# OSCILLAR_HFB_V1p0_AFILT.net
KiCad netlist of a schematic drawn in Altium Designer
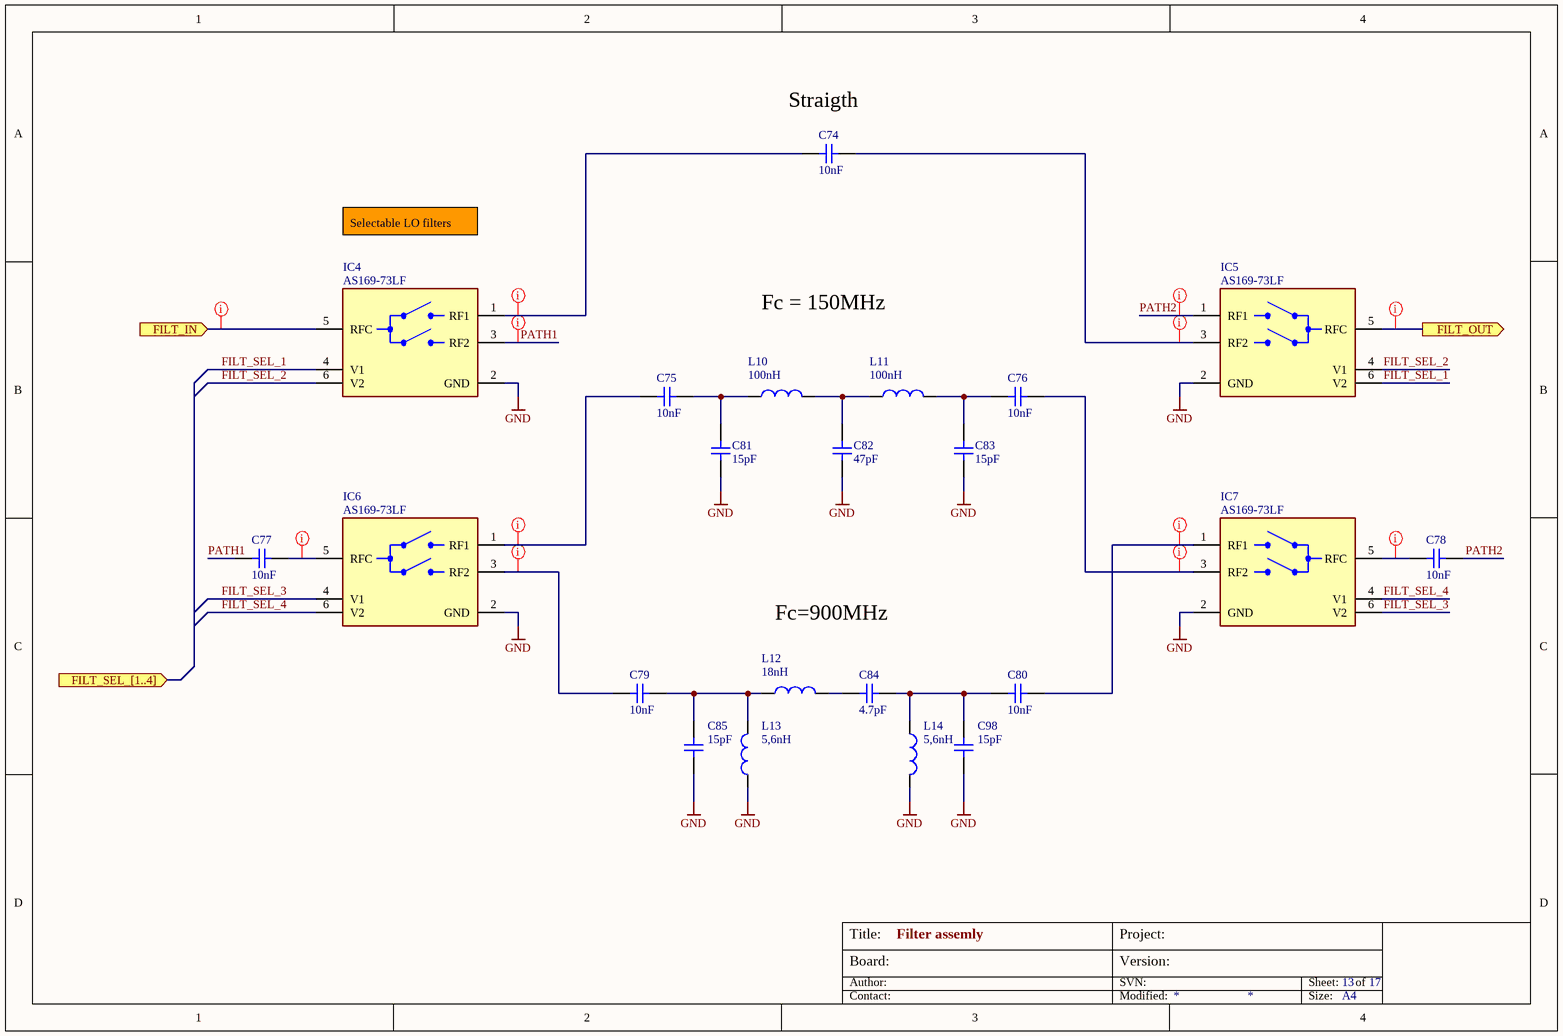
[diagram p0: OSCILLAR_HFB_V1p0_AFILT.SchDoc]

(export (version "E")
  (design (tool "Eeschema 10.0.6"))
  (components
    (comp (ref "C74")
      (value "10nF")
      (footprint "CAP_0603")
      (description "MLCC capacitor")
      (libsource (lib "SCHLIB") (part "NP-CAPACITOR"))
    )
    (comp (ref "C75")
      (value "10nF")
      (footprint "CAP_0603")
      (description "MLCC capacitor")
      (libsource (lib "SCHLIB") (part "NP-CAPACITOR"))
    )
    (comp (ref "C76")
      (value "10nF")
      (footprint "CAP_0603")
      (description "MLCC capacitor")
      (libsource (lib "SCHLIB") (part "NP-CAPACITOR"))
    )
    (comp (ref "C77")
      (value "10nF")
      (footprint "CAP_0603")
      (description "MLCC capacitor")
      (libsource (lib "SCHLIB") (part "NP-CAPACITOR"))
    )
    (comp (ref "C78")
      (value "10nF")
      (footprint "CAP_0603")
      (description "MLCC capacitor")
      (libsource (lib "SCHLIB") (part "NP-CAPACITOR"))
    )
    (comp (ref "C79")
      (value "10nF")
      (footprint "CAP_0603")
      (description "MLCC capacitor")
      (libsource (lib "SCHLIB") (part "NP-CAPACITOR"))
    )
    (comp (ref "C80")
      (value "10nF")
      (footprint "CAP_0603")
      (description "MLCC capacitor")
      (libsource (lib "SCHLIB") (part "NP-CAPACITOR"))
    )
    (comp (ref "C81")
      (value "15pF")
      (footprint "CAP_0603")
      (description "MLCC capacitor")
      (libsource (lib "SCHLIB") (part "NP-CAPACITOR"))
    )
    (comp (ref "C82")
      (value "47pF")
      (footprint "CAP_0603")
      (description "MLCC capacitor")
      (libsource (lib "SCHLIB") (part "NP-CAPACITOR"))
    )
    (comp (ref "C83")
      (value "15pF")
      (footprint "CAP_0603")
      (description "MLCC capacitor")
      (libsource (lib "SCHLIB") (part "NP-CAPACITOR"))
    )
    (comp (ref "C84")
      (value "4.7pF")
      (footprint "CAP_0603")
      (description "MLCC capacitor")
      (libsource (lib "SCHLIB") (part "NP-CAPACITOR"))
    )
    (comp (ref "C85")
      (value "15pF")
      (footprint "CAP_0603")
      (description "MLCC capacitor")
      (libsource (lib "SCHLIB") (part "NP-CAPACITOR"))
    )
    (comp (ref "C98")
      (value "15pF")
      (footprint "CAP_0603")
      (description "MLCC capacitor")
      (libsource (lib "SCHLIB") (part "NP-CAPACITOR"))
    )
    (comp (ref "IC4")
      (value "AS169-73LF")
      (footprint "SOT-23-6")
      (description "RF Switch, SPDT, 300k-2.5GHz")
      (fields (field (name "PART NUMBER") "873-AS169-73LF"))
      (libsource (lib "") (part "AS169-73LF_1"))
    )
    (comp (ref "IC5")
      (value "AS169-73LF")
      (footprint "SOT-23-6")
      (description "RF Switch, SPDT, 300k-2.5GHz")
      (fields (field (name "PART NUMBER") "873-AS169-73LF"))
      (libsource (lib "SCHLIB") (part "AS169-73LF"))
    )
    (comp (ref "IC6")
      (value "AS169-73LF")
      (footprint "SOT-23-6")
      (description "RF Switch, SPDT, 300k-2.5GHz")
      (fields (field (name "PART NUMBER") "873-AS169-73LF"))
      (libsource (lib "") (part "AS169-73LF_1"))
    )
    (comp (ref "IC7")
      (value "AS169-73LF")
      (footprint "SOT-23-6")
      (description "RF Switch, SPDT, 300k-2.5GHz")
      (fields (field (name "PART NUMBER") "873-AS169-73LF"))
      (libsource (lib "SCHLIB") (part "AS169-73LF"))
    )
    (comp (ref "L10")
      (value "100nH")
      (footprint "IND-0805")
      (description "IMC0805ERR10J01")
      (libsource (lib "SCHLIB") (part "AC-INDUCTOR"))
    )
    (comp (ref "L11")
      (value "100nH")
      (footprint "IND-0805")
      (description "IMC0805ERR10J01")
      (libsource (lib "SCHLIB") (part "AC-INDUCTOR"))
    )
    (comp (ref "L12")
      (value "18nH")
      (footprint "IND-0805")
      (description "IMC0805ER18NJ01")
      (libsource (lib "SCHLIB") (part "AC-INDUCTOR"))
    )
    (comp (ref "L13")
      (value "5,6nH")
      (footprint "IND-0805")
      (description "IMC0805ER5N6J01")
      (libsource (lib "SCHLIB") (part "AC-INDUCTOR"))
    )
    (comp (ref "L14")
      (value "5,6nH")
      (footprint "IND-0805")
      (description "IMC0805ER5N6J01")
      (libsource (lib "") (part "AC-INDUCTOR_1"))
    )
  )
  (nets
    (net (code "1") (name "/FILT_IN") (class "Default")
      (node (ref "IC4") (pin "5") (pinfunction "RFC_5") (pintype "passive"))
    )
    (net (code "2") (name "/FILT_OUT") (class "Default")
      (node (ref "IC5") (pin "5") (pinfunction "RFC_5") (pintype "passive"))
    )
    (net (code "3") (name "/FILT_SEL_1") (class "Default")
      (node (ref "IC4") (pin "4") (pinfunction "V1_4") (pintype "passive"))
      (node (ref "IC5") (pin "6") (pinfunction "V2_6") (pintype "passive"))
    )
    (net (code "4") (name "/FILT_SEL_2") (class "Default")
      (node (ref "IC4") (pin "6") (pinfunction "V2_6") (pintype "passive"))
      (node (ref "IC5") (pin "4") (pinfunction "V1_4") (pintype "passive"))
    )
    (net (code "5") (name "/FILT_SEL_3") (class "Default")
      (node (ref "IC6") (pin "4") (pinfunction "V1_4") (pintype "passive"))
      (node (ref "IC7") (pin "6") (pinfunction "V2_6") (pintype "passive"))
    )
    (net (code "6") (name "/FILT_SEL_4") (class "Default")
      (node (ref "IC6") (pin "6") (pinfunction "V2_6") (pintype "passive"))
      (node (ref "IC7") (pin "4") (pinfunction "V1_4") (pintype "passive"))
    )
    (net (code "8") (name "/PATH1") (class "Default")
      (node (ref "C77") (pin "2") (pinfunction "2_2") (pintype "passive"))
      (node (ref "IC4") (pin "3") (pinfunction "RF2_3") (pintype "passive"))
    )
    (net (code "9") (name "/PATH2") (class "Default")
      (node (ref "C78") (pin "1") (pinfunction "1_1") (pintype "passive"))
      (node (ref "IC5") (pin "1") (pinfunction "RF1_1") (pintype "passive"))
    )
    (net (code "10") (name "GND") (class "Default")
      (node (ref "C81") (pin "1") (pinfunction "1_1") (pintype "passive"))
      (node (ref "C82") (pin "1") (pinfunction "1_1") (pintype "passive"))
      (node (ref "C83") (pin "1") (pinfunction "1_1") (pintype "passive"))
      (node (ref "C85") (pin "2") (pinfunction "2_2") (pintype "passive"))
      (node (ref "C98") (pin "2") (pinfunction "2_2") (pintype "passive"))
      (node (ref "IC4") (pin "2") (pinfunction "GND_2") (pintype "passive"))
      (node (ref "IC5") (pin "2") (pinfunction "GND_2") (pintype "passive"))
      (node (ref "IC6") (pin "2") (pinfunction "GND_2") (pintype "passive"))
      (node (ref "IC7") (pin "2") (pinfunction "GND_2") (pintype "passive"))
      (node (ref "L13") (pin "1") (pinfunction "1_1") (pintype "passive"))
      (node (ref "L14") (pin "1") (pinfunction "1_1") (pintype "passive"))
    )
    (net (code "11") (name "Net-(C75-Pad1)") (class "Default")
      (node (ref "C75") (pin "1") (pinfunction "1_1") (pintype "passive"))
      (node (ref "C81") (pin "2") (pinfunction "2_2") (pintype "passive"))
      (node (ref "L10") (pin "1") (pinfunction "1_1") (pintype "passive"))
    )
    (net (code "12") (name "Net-(C76-Pad2)") (class "Default")
      (node (ref "C76") (pin "2") (pinfunction "2_2") (pintype "passive"))
      (node (ref "C83") (pin "2") (pinfunction "2_2") (pintype "passive"))
      (node (ref "L11") (pin "2") (pinfunction "2_2") (pintype "passive"))
    )
    (net (code "13") (name "Net-(C79-Pad1)") (class "Default")
      (node (ref "C79") (pin "1") (pinfunction "1_1") (pintype "passive"))
      (node (ref "C85") (pin "1") (pinfunction "1_1") (pintype "passive"))
      (node (ref "L12") (pin "1") (pinfunction "1_1") (pintype "passive"))
      (node (ref "L13") (pin "2") (pinfunction "2_2") (pintype "passive"))
    )
    (net (code "14") (name "Net-(C80-Pad2)") (class "Default")
      (node (ref "C80") (pin "2") (pinfunction "2_2") (pintype "passive"))
      (node (ref "C84") (pin "1") (pinfunction "1_1") (pintype "passive"))
      (node (ref "C98") (pin "1") (pinfunction "1_1") (pintype "passive"))
      (node (ref "L14") (pin "2") (pinfunction "2_2") (pintype "passive"))
    )
    (net (code "15") (name "Net-(C82-Pad2)") (class "Default")
      (node (ref "C82") (pin "2") (pinfunction "2_2") (pintype "passive"))
      (node (ref "L10") (pin "2") (pinfunction "2_2") (pintype "passive"))
      (node (ref "L11") (pin "1") (pinfunction "1_1") (pintype "passive"))
    )
    (net (code "16") (name "Net-(C84-Pad2)") (class "Default")
      (node (ref "C84") (pin "2") (pinfunction "2_2") (pintype "passive"))
      (node (ref "L12") (pin "2") (pinfunction "2_2") (pintype "passive"))
    )
    (net (code "17") (name "Net-(IC4-RF1)") (class "Default")
      (node (ref "C74") (pin "2") (pinfunction "2_2") (pintype "passive"))
      (node (ref "IC4") (pin "1") (pinfunction "RF1_1") (pintype "passive"))
    )
    (net (code "18") (name "Net-(IC5-RF2)") (class "Default")
      (node (ref "C74") (pin "1") (pinfunction "1_1") (pintype "passive"))
      (node (ref "IC5") (pin "3") (pinfunction "RF2_3") (pintype "passive"))
    )
    (net (code "19") (name "Net-(IC6-RF1)") (class "Default")
      (node (ref "C75") (pin "2") (pinfunction "2_2") (pintype "passive"))
      (node (ref "IC6") (pin "1") (pinfunction "RF1_1") (pintype "passive"))
    )
    (net (code "20") (name "Net-(IC6-RF2)") (class "Default")
      (node (ref "C79") (pin "2") (pinfunction "2_2") (pintype "passive"))
      (node (ref "IC6") (pin "3") (pinfunction "RF2_3") (pintype "passive"))
    )
    (net (code "21") (name "Net-(IC6-RFC)") (class "Default")
      (node (ref "C77") (pin "1") (pinfunction "1_1") (pintype "passive"))
      (node (ref "IC6") (pin "5") (pinfunction "RFC_5") (pintype "passive"))
    )
    (net (code "22") (name "Net-(IC7-RF1)") (class "Default")
      (node (ref "C80") (pin "1") (pinfunction "1_1") (pintype "passive"))
      (node (ref "IC7") (pin "1") (pinfunction "RF1_1") (pintype "passive"))
    )
    (net (code "23") (name "Net-(IC7-RF2)") (class "Default")
      (node (ref "C76") (pin "1") (pinfunction "1_1") (pintype "passive"))
      (node (ref "IC7") (pin "3") (pinfunction "RF2_3") (pintype "passive"))
    )
    (net (code "24") (name "Net-(IC7-RFC)") (class "Default")
      (node (ref "C78") (pin "2") (pinfunction "2_2") (pintype "passive"))
      (node (ref "IC7") (pin "5") (pinfunction "RFC_5") (pintype "passive"))
    )
  )
)
